# Drone.net
KiCad netlist of a schematic drawn in Altium Designer
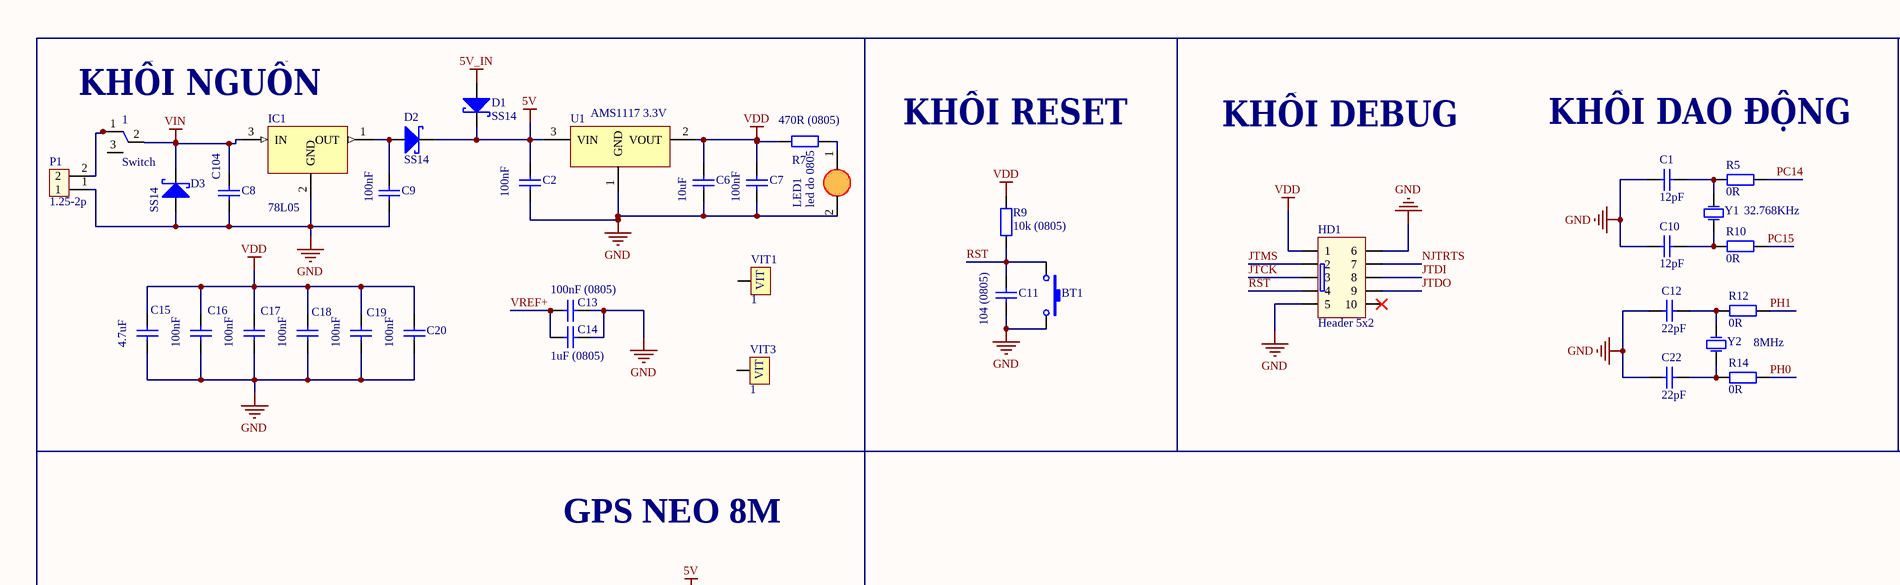
[diagram p0: Drone.SchDoc, top left]
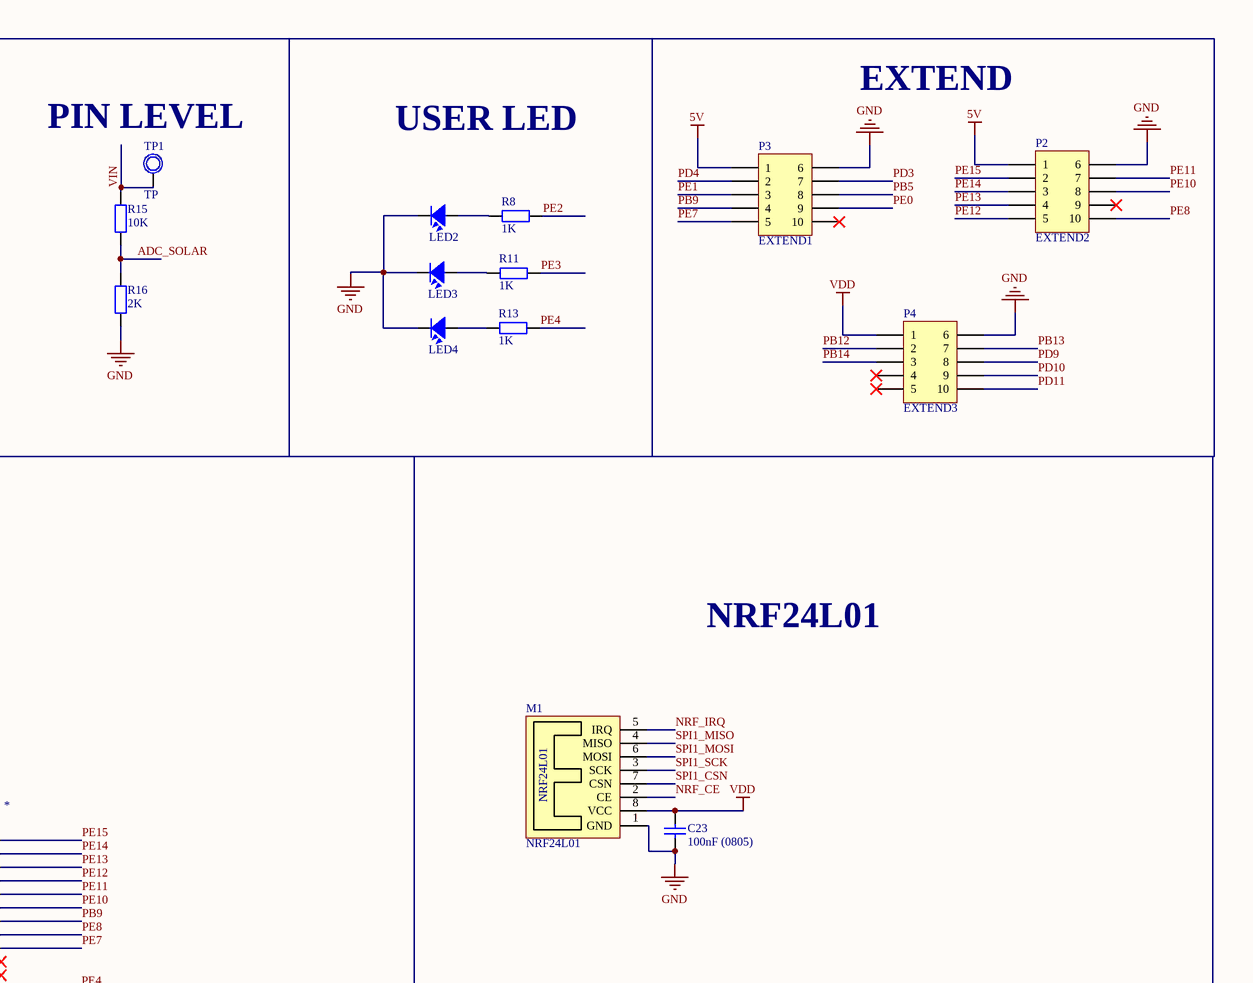
[diagram p1: Drone.SchDoc, top right]
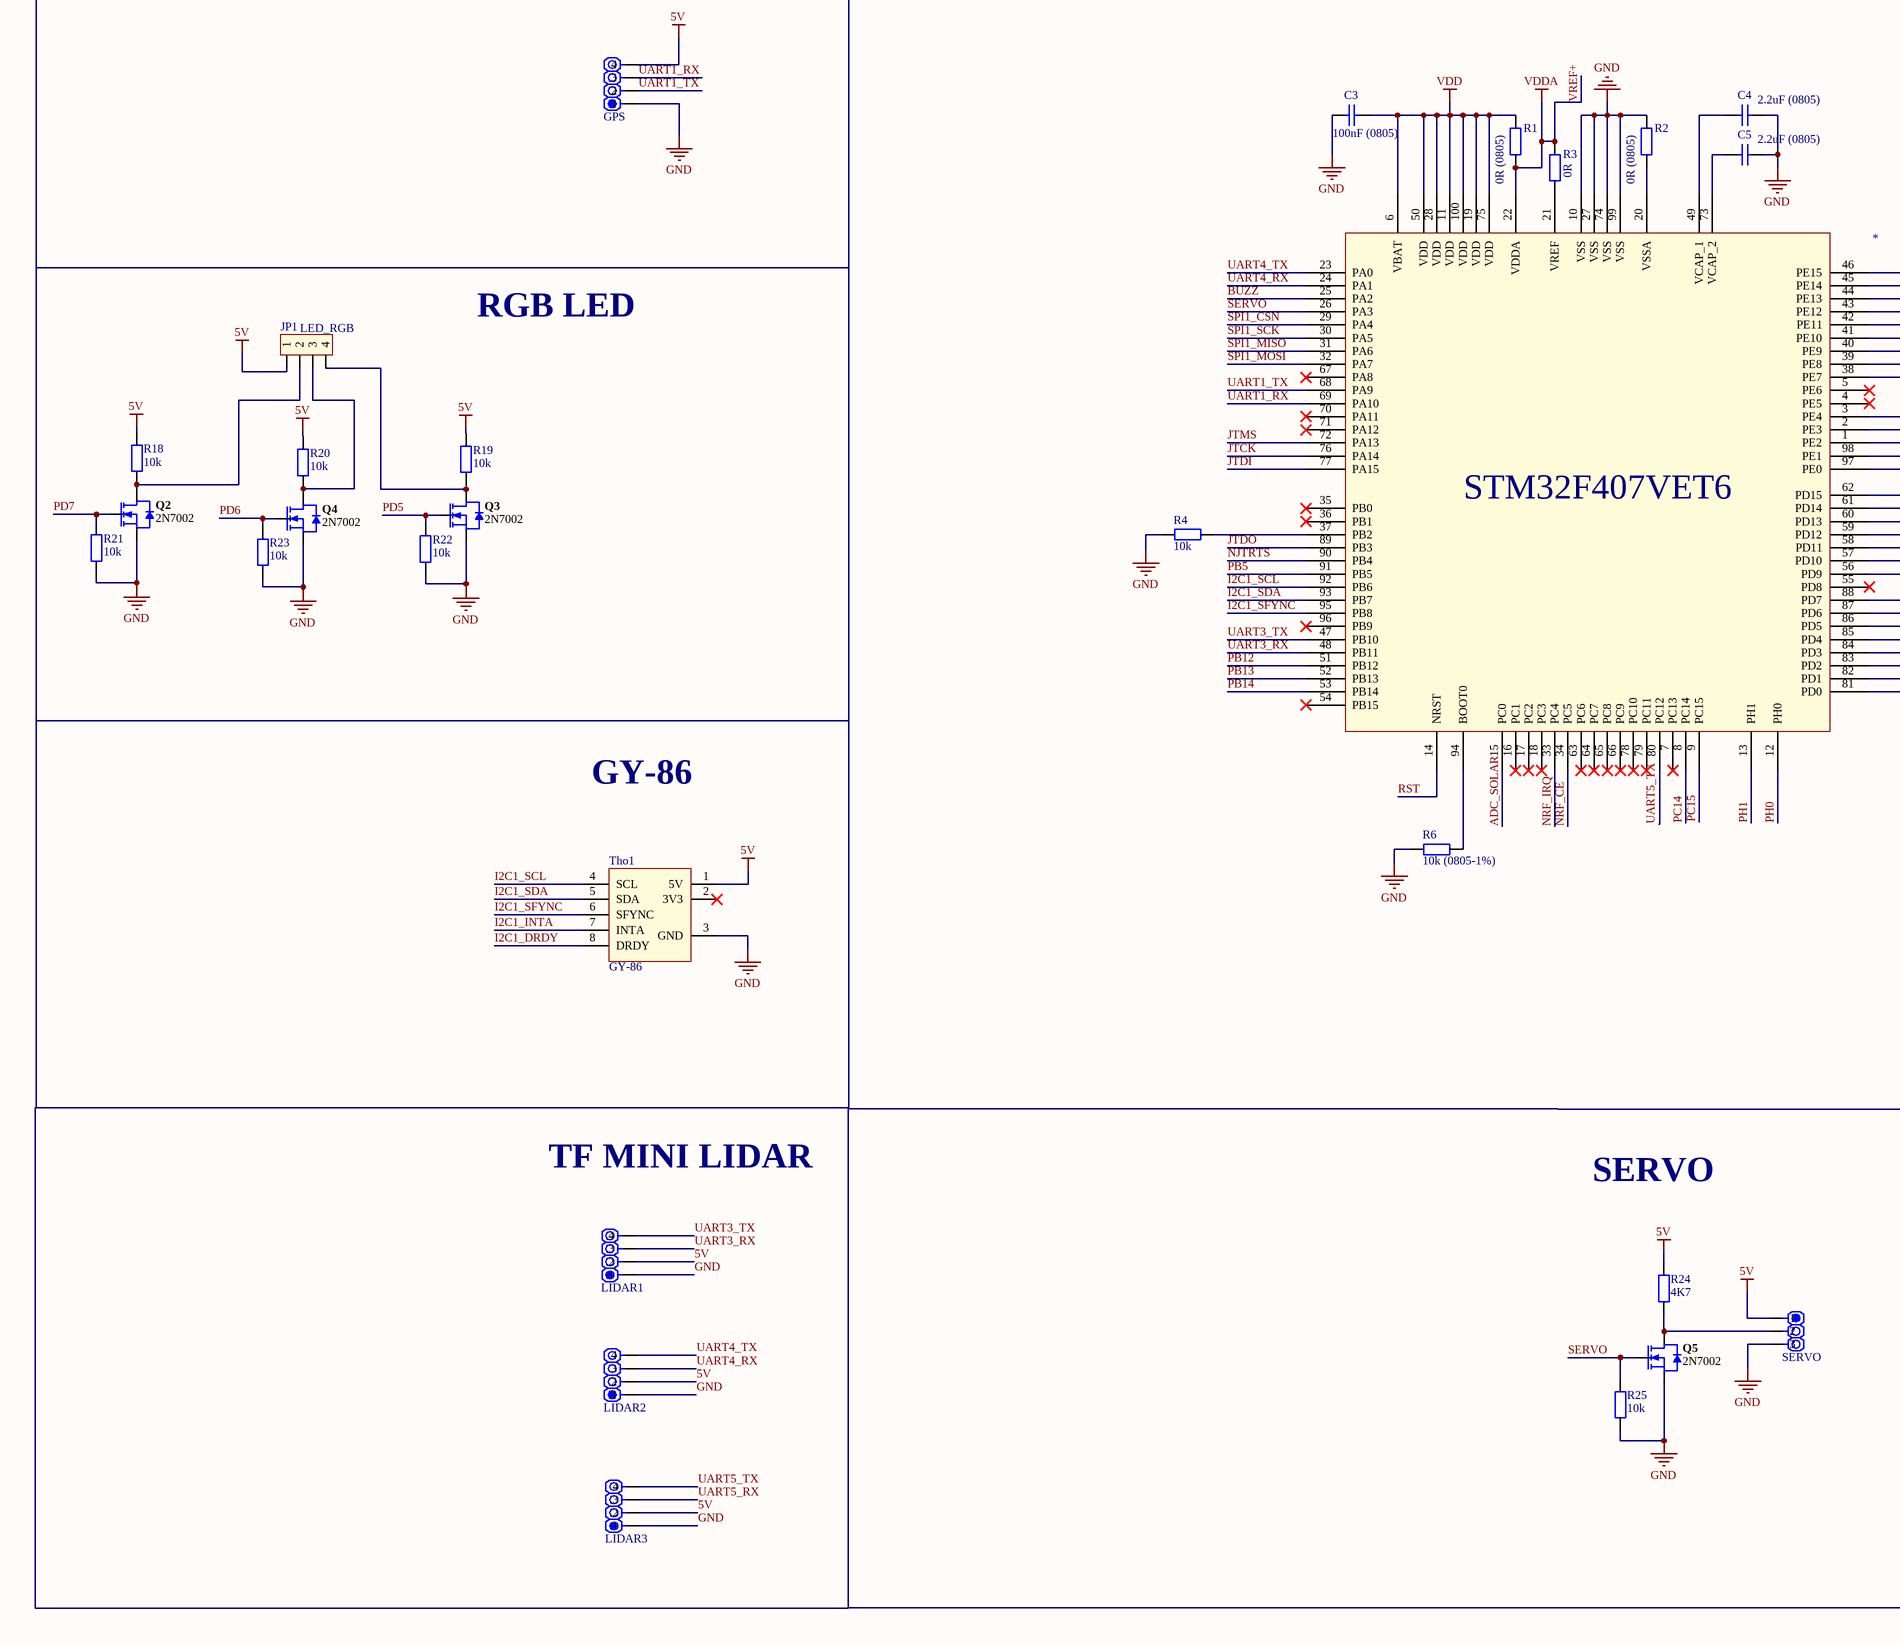
[diagram p2: Drone.SchDoc, bottom left]
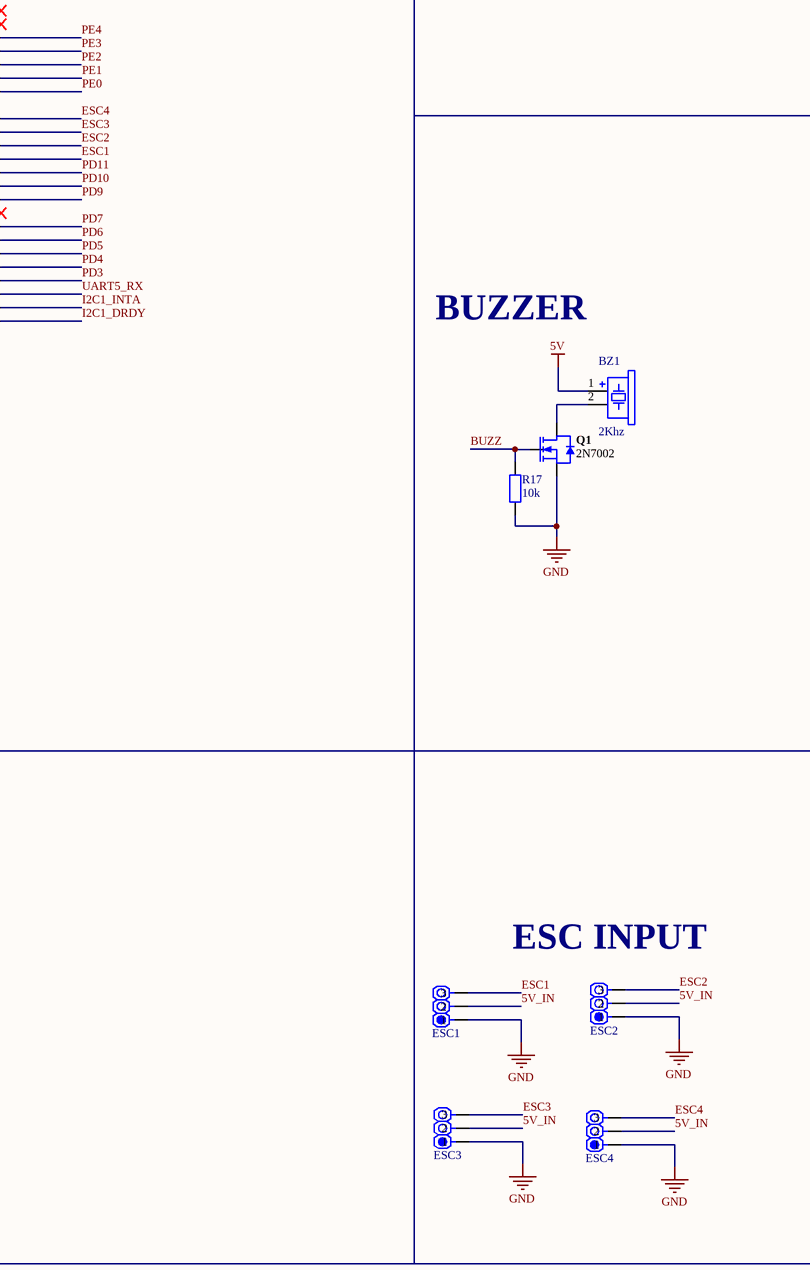
[diagram p3: Drone.SchDoc, bottom right]

(export (version "E")
  (design (tool "Eeschema 10.0.6"))
  (components
    (comp (ref "*")
      (value "STM32F407")
      (footprint "STM32F407Vet6")
      (libsource (lib "STM32f407") (part "STM32F407"))
    )
    (comp (ref "1") (value "Switch") (footprint "SW_MSS") (libsource (lib "JOYSTICK") (part "Switch")))
    (comp (ref "BT1")
      (value "Nút Nhấn 2 Chân 3x6x2.5MM SMD")
      (footprint "Nut Nhan 2 Chan SMD_N")
      (description "Dán")
      (libsource (lib "SCH Chuan") (part "Nut Nhan 2 Chan SMD"))
    )
    (comp (ref "BZ1")
      (value "2Khz")
      (footprint "coi xung")
      (description "Cắm")
      (libsource (lib "SCH Chuan") (part "Coi xung 2Khz"))
    )
    (comp (ref "C1")
      (value "12pF")
      (footprint "tu 0805")
      (description "Dán")
      (libsource (lib "SCH Chuan") (part "Tu 0805 10pF 50V 10%"))
    )
    (comp (ref "C2")
      (value "100nF")
      (footprint "tu 0805")
      (description "Dán")
      (libsource (lib "SCH Chuan") (part "Tu 0805 104 50V 10%"))
    )
    (comp (ref "C3")
      (value "100nF (0805)")
      (footprint "tu 0805")
      (description "Dán")
      (libsource (lib "SCH Chuan") (part "Tu 0805 220nF 50V 10%"))
    )
    (comp (ref "C4")
      (value "2.2uF (0805)")
      (footprint "tu 0805")
      (description "Dán")
      (libsource (lib "SCH Chuan") (part "Tu 0805 220nF 50V 10%"))
    )
    (comp (ref "C5")
      (value "2.2uF (0805)")
      (footprint "tu 0805")
      (description "Dán")
      (libsource (lib "SCH Chuan") (part "Tu 0805 220nF 50V 10%"))
    )
    (comp (ref "C6")
      (value "10uF")
      (footprint "tu 0805")
      (description "Dán")
      (libsource (lib "SCH Chuan") (part "Tu 0805 104 50V 10%"))
    )
    (comp (ref "C7")
      (value "100nF")
      (footprint "tu 0805")
      (description "Dán")
      (libsource (lib "SCH Chuan") (part "Tu 0805 104 50V 10%"))
    )
    (comp (ref "C8")
      (value "C104")
      (footprint "tu 0805")
      (description "Dán")
      (libsource (lib "SCH Chuan") (part "Tu 0805 104 50V 10%"))
    )
    (comp (ref "C9")
      (value "100nF")
      (footprint "tu 0805")
      (description "Dán")
      (libsource (lib "SCH Chuan") (part "Tu 0805 104 50V 10%"))
    )
    (comp (ref "C10")
      (value "12pF")
      (footprint "tu 0805")
      (description "Dán")
      (libsource (lib "SCH Chuan") (part "Tu 0805 10pF 50V 10%"))
    )
    (comp (ref "C11")
      (value "104 (0805)")
      (footprint "tu 0805")
      (description "Dán")
      (libsource (lib "SCH Chuan") (part "Tu 0805 104 50V 10%"))
    )
    (comp (ref "C12")
      (value "22pF")
      (footprint "tu 0805")
      (description "Dán")
      (libsource (lib "SCH Chuan") (part "Tu 0805 10pF 50V 10%"))
    )
    (comp (ref "C13")
      (value "100nF (0805)")
      (footprint "tu 0805")
      (description "Dán")
      (libsource (lib "SCH Chuan") (part "Tu 0805 220nF 50V 10%"))
    )
    (comp (ref "C14")
      (value "1uF (0805)")
      (footprint "tu 0805")
      (description "Dán")
      (libsource (lib "SCH Chuan") (part "Tu 0805 220nF 50V 10%"))
    )
    (comp (ref "C15")
      (value "4.7uF")
      (footprint "tu 0805")
      (description "Dán")
      (libsource (lib "SCH Chuan") (part "Tu 0805 104 50V 10%"))
    )
    (comp (ref "C16")
      (value "100nF")
      (footprint "tu 0805")
      (description "Dán")
      (libsource (lib "SCH Chuan") (part "Tu 0805 104 50V 10%"))
    )
    (comp (ref "C17")
      (value "100nF")
      (footprint "tu 0805")
      (description "Dán")
      (libsource (lib "SCH Chuan") (part "Tu 0805 104 50V 10%"))
    )
    (comp (ref "C18")
      (value "100nF")
      (footprint "tu 0805")
      (description "Dán")
      (libsource (lib "SCH Chuan") (part "Tu 0805 104 50V 10%"))
    )
    (comp (ref "C19")
      (value "100nF")
      (footprint "tu 0805")
      (description "Dán")
      (libsource (lib "SCH Chuan") (part "Tu 0805 104 50V 10%"))
    )
    (comp (ref "C20")
      (value "100nF")
      (footprint "tu 0805")
      (description "Dán")
      (libsource (lib "SCH Chuan") (part "Tu 0805 104 50V 10%"))
    )
    (comp (ref "C22")
      (value "22pF")
      (footprint "tu 0805")
      (description "Dán")
      (libsource (lib "SCH Chuan") (part "Tu 0805 10pF 50V 10%"))
    )
    (comp (ref "C23")
      (value "100nF (0805)")
      (footprint "tu 0805")
      (description "Dán")
      (libsource (lib "SCH Chuan") (part "Tu 0805 220nF 50V 10%"))
    )
    (comp (ref "D1")
      (value "SS14")
      (footprint "DIODE SMD")
      (description "Dán")
      (libsource (lib "SCH Chuan") (part "Diode SS14 ( 1N5819)"))
    )
    (comp (ref "D2")
      (value "SS14")
      (footprint "DIODE SMD")
      (description "Dán")
      (libsource (lib "SCH Chuan") (part "Diode SS14 ( 1N5819)"))
    )
    (comp (ref "D3")
      (value "SS14")
      (footprint "DIODE SMD")
      (description "Dán")
      (libsource (lib "SCH Chuan") (part "Diode SS14 ( 1N5819)"))
    )
    (comp (ref "ESC1")
      (value "IO")
      (footprint "CON.HDR1X3")
      (description "Header 1x3")
      (fields (field (name "PUBLISHER") "NKIM"))
      (libsource (lib "VPMyLibrary") (part "CON.HDR1x3"))
    )
    (comp (ref "ESC2")
      (value "IO")
      (footprint "CON.HDR1X3")
      (description "Header 1x3")
      (fields (field (name "PUBLISHER") "NKIM"))
      (libsource (lib "VPMyLibrary") (part "CON.HDR1x3"))
    )
    (comp (ref "ESC3")
      (value "IO")
      (footprint "CON.HDR1X3")
      (description "Header 1x3")
      (fields (field (name "PUBLISHER") "NKIM"))
      (libsource (lib "VPMyLibrary") (part "CON.HDR1x3"))
    )
    (comp (ref "ESC4")
      (value "IO")
      (footprint "CON.HDR1X3")
      (description "Header 1x3")
      (fields (field (name "PUBLISHER") "NKIM"))
      (libsource (lib "VPMyLibrary") (part "CON.HDR1x3"))
    )
    (comp (ref "GPS")
      (value "IO")
      (footprint "CON.HDR1X4L")
      (description "Header 1x4")
      (fields (field (name "PUBLISHER") "NKIM"))
      (libsource (lib "VPMyLibrary") (part "CON.HDR1x4"))
    )
    (comp (ref "HD1")
      (value "Header 5x2")
      (footprint "Hed2X5")
      (libsource (lib "syhaunguyen") (part "HED5x2"))
    )
    (comp (ref "IC1")
      (value "78L05")
      (footprint "SOT89-150P410X160-3N")
      (description "Dán")
      (libsource (lib "SCH Chuan") (part "78L05"))
    )
    (comp (ref "JP1")
      (value "LED_RGB")
      (footprint "JUMP DON DUC 2.54_4P")
      (description "Cắm")
      (libsource (lib "NhomLib") (part "Jump Don Duc 2.54_4P"))
    )
    (comp (ref "LED1")
      (value "led do 0805")
      (footprint "led 0805")
      (description "Dán")
      (libsource (lib "SCH Chuan") (part "Led 0805 Do"))
    )
    (comp (ref "LED2")
      (value "LED SMD")
      (footprint "SM-LED-0805-Yellow")
      (libsource (lib "syhaunguyen") (part "LED-SMD-0805"))
    )
    (comp (ref "LED3")
      (value "LED SMD")
      (footprint "SM-LED-0805-Green")
      (libsource (lib "syhaunguyen") (part "LED-SMD-0805"))
    )
    (comp (ref "LED4")
      (value "LED SMD")
      (footprint "SM-LED-0805-Blue")
      (libsource (lib "syhaunguyen") (part "LED-SMD-0805"))
    )
    (comp (ref "LIDAR1")
      (value "IO")
      (footprint "CON.HDR1X4L")
      (description "Header 1x4")
      (fields (field (name "PUBLISHER") "NKIM"))
      (libsource (lib "VPMyLibrary") (part "CON.HDR1x4"))
    )
    (comp (ref "LIDAR2")
      (value "IO")
      (footprint "CON.HDR1X4L")
      (description "Header 1x4")
      (fields (field (name "PUBLISHER") "NKIM"))
      (libsource (lib "VPMyLibrary") (part "CON.HDR1x4"))
    )
    (comp (ref "LIDAR3")
      (value "IO")
      (footprint "CON.HDR1X4L")
      (description "Header 1x4")
      (fields (field (name "PUBLISHER") "NKIM"))
      (libsource (lib "VPMyLibrary") (part "CON.HDR1x4"))
    )
    (comp (ref "M1") (value "NRF24L01") (footprint "NRF24L01") (libsource (lib "LIBRARY") (part "NRF24L01")))
    (comp (ref "P1")
      (value "1.25-2p")
      (footprint "Header Duc Thang 2p 1.25")
      (description "Cắm")
      (libsource (lib "SCH Chuan") (part "Header 1.25-2p"))
    )
    (comp (ref "P2")
      (value "EXTEND2")
      (footprint "HDR2X5_CEN")
      (description "Header, 5-Pin, Dual row")
      (fields (field (name "PUBLISHER") "Altium Limited"))
      (libsource (lib "NBBLib 14-03-2012") (part "Header 5X2A"))
    )
    (comp (ref "P3")
      (value "EXTEND1")
      (footprint "HDR2X5_CEN")
      (description "Header, 5-Pin, Dual row")
      (fields (field (name "PUBLISHER") "Altium Limited"))
      (libsource (lib "NBBLib 14-03-2012") (part "Header 5X2A"))
    )
    (comp (ref "P4")
      (value "EXTEND3")
      (footprint "HDR2X5_CEN")
      (description "Header, 5-Pin, Dual row")
      (fields (field (name "PUBLISHER") "Altium Limited"))
      (libsource (lib "NBBLib 14-03-2012") (part "Header 5X2A"))
    )
    (comp (ref "Q1")
      (value "2N7002")
      (footprint "SOT23-123")
      (description "N-channel Enhancement Mode Field-effect Transistor")
      (libsource (lib "LIBRARY") (part "2N7002"))
    )
    (comp (ref "Q2")
      (value "2N7002")
      (footprint "SOT23-123")
      (description "N-channel Enhancement Mode Field-effect Transistor")
      (libsource (lib "LIBRARY") (part "2N7002"))
    )
    (comp (ref "Q3")
      (value "2N7002")
      (footprint "SOT23-123")
      (description "N-channel Enhancement Mode Field-effect Transistor")
      (libsource (lib "LIBRARY") (part "2N7002"))
    )
    (comp (ref "Q4")
      (value "2N7002")
      (footprint "SOT23-123")
      (description "N-channel Enhancement Mode Field-effect Transistor")
      (libsource (lib "LIBRARY") (part "2N7002"))
    )
    (comp (ref "Q5")
      (value "2N7002")
      (footprint "SOT23-123")
      (description "N-channel Enhancement Mode Field-effect Transistor")
      (libsource (lib "LIBRARY") (part "2N7002"))
    )
    (comp (ref "R1")
      (value "0R (0805)")
      (footprint "tro 0805")
      (description "Dán")
      (libsource (lib "SCH Chuan") (part "Tro 0805 5% 470R"))
    )
    (comp (ref "R2")
      (value "0R (0805)")
      (footprint "tro 0805")
      (description "Dán")
      (libsource (lib "SCH Chuan") (part "Tro 0805 5% 470R"))
    )
    (comp (ref "R3")
      (value "0R")
      (footprint "tro 0805")
      (description "Dán")
      (libsource (lib "SCH Chuan") (part "Tro 0805 5% 470R"))
    )
    (comp (ref "R4")
      (value "10k")
      (footprint "tro 0805")
      (description "Dán")
      (libsource (lib "SCH Chuan") (part "Tro 0805 1% 10k"))
    )
    (comp (ref "R5")
      (value "0R")
      (footprint "tro 0805")
      (description "Dán")
      (libsource (lib "SCH Chuan") (part "Tro 0805 5% 470R"))
    )
    (comp (ref "R6")
      (value "10k (0805-1%)")
      (footprint "tro 0805")
      (description "Dán")
      (libsource (lib "SCH Chuan") (part "Tro 0805 1% 10k"))
    )
    (comp (ref "R7")
      (value "470R (0805)")
      (footprint "tro 0805")
      (description "Dán")
      (libsource (lib "SCH Chuan") (part "Tro 0805 5% 470R"))
    )
    (comp (ref "R8")
      (value "1K")
      (footprint "tro 0805")
      (description "Dán")
      (libsource (lib "SCH Chuan") (part "Tro 0805 5% 470R"))
    )
    (comp (ref "R9")
      (value "10k (0805)")
      (footprint "tro 0805")
      (description "Dán")
      (libsource (lib "SCH Chuan") (part "Tro 0805 5% 10k"))
    )
    (comp (ref "R10")
      (value "0R")
      (footprint "tro 0805")
      (description "Dán")
      (libsource (lib "SCH Chuan") (part "Tro 0805 5% 470R"))
    )
    (comp (ref "R11")
      (value "1K")
      (footprint "tro 0805")
      (description "Dán")
      (libsource (lib "SCH Chuan") (part "Tro 0805 5% 470R"))
    )
    (comp (ref "R12")
      (value "0R")
      (footprint "tro 0805")
      (description "Dán")
      (libsource (lib "SCH Chuan") (part "Tro 0805 5% 470R"))
    )
    (comp (ref "R13")
      (value "1K")
      (footprint "tro 0805")
      (description "Dán")
      (libsource (lib "SCH Chuan") (part "Tro 0805 5% 470R"))
    )
    (comp (ref "R14")
      (value "0R")
      (footprint "tro 0805")
      (description "Dán")
      (libsource (lib "SCH Chuan") (part "Tro 0805 5% 470R"))
    )
    (comp (ref "R15")
      (value "10K")
      (footprint "tro 0805")
      (description "Dán")
      (libsource (lib "SCH Chuan") (part "Tro 0805 5% 10k"))
    )
    (comp (ref "R16")
      (value "2K")
      (footprint "tro 0805")
      (description "Dán")
      (libsource (lib "SCH Chuan") (part "Tro 0805 5% 10k"))
    )
    (comp (ref "R17")
      (value "10k")
      (footprint "tro 0805")
      (description "Dán")
      (libsource (lib "SCH Chuan") (part "Tro 0805 1% 10k"))
    )
    (comp (ref "R18")
      (value "10k")
      (footprint "tro 0805")
      (description "Dán")
      (libsource (lib "SCH Chuan") (part "Tro 0805 1% 10k"))
    )
    (comp (ref "R19")
      (value "10k")
      (footprint "tro 0805")
      (description "Dán")
      (libsource (lib "SCH Chuan") (part "Tro 0805 1% 10k"))
    )
    (comp (ref "R20")
      (value "10k")
      (footprint "tro 0805")
      (description "Dán")
      (libsource (lib "SCH Chuan") (part "Tro 0805 1% 10k"))
    )
    (comp (ref "R21")
      (value "10k")
      (footprint "tro 0805")
      (description "Dán")
      (libsource (lib "SCH Chuan") (part "Tro 0805 1% 10k"))
    )
    (comp (ref "R22")
      (value "10k")
      (footprint "tro 0805")
      (description "Dán")
      (libsource (lib "SCH Chuan") (part "Tro 0805 1% 10k"))
    )
    (comp (ref "R23")
      (value "10k")
      (footprint "tro 0805")
      (description "Dán")
      (libsource (lib "SCH Chuan") (part "Tro 0805 1% 10k"))
    )
    (comp (ref "R24")
      (value "4K7")
      (footprint "tro 0805")
      (description "Dán")
      (libsource (lib "SCH Chuan") (part "Tro 0805 1% 10k"))
    )
    (comp (ref "R25")
      (value "10k")
      (footprint "tro 0805")
      (description "Dán")
      (libsource (lib "SCH Chuan") (part "Tro 0805 1% 10k"))
    )
    (comp (ref "SERVO")
      (value "IO")
      (footprint "CON.HDR1X3")
      (description "Header 1x3")
      (fields (field (name "PUBLISHER") "NKIM"))
      (libsource (lib "VPMyLibrary") (part "CON.HDR1x3"))
    )
    (comp (ref "Tho1") (value "GY-86") (footprint "GY-86") (libsource (lib "JOYSTICK") (part "GY-86")))
    (comp (ref "TP1")
      (value "TP")
      (footprint "TP1")
      (description "Test Point")
      (libsource (lib "syhaunguyen") (part "TP1"))
    )
    (comp (ref "U1")
      (value "AMS1117 3.3V")
      (footprint "SOT223")
      (description "Dán")
      (libsource (lib "SCH Chuan") (part "AMS1117 3.3V"))
    )
    (comp (ref "VIT1")
      (value "1")
      (footprint "VIT")
      (description "Oc Vit")
      (libsource (lib "LIBRARY") (part "VIT"))
    )
    (comp (ref "VIT3")
      (value "1")
      (footprint "VIT")
      (description "Oc Vit")
      (libsource (lib "LIBRARY") (part "VIT"))
    )
    (comp (ref "Y1")
      (value "32.768KHz")
      (footprint "XT2-32.768KHz-2_V")
      (description "Dán")
      (libsource (lib "SCH Chuan") (part "Thach anh 8MHz 49S SMD"))
    )
    (comp (ref "Y2")
      (value "8MHz")
      (footprint "thach anh 49s smd")
      (description "Dán")
      (libsource (lib "SCH Chuan") (part "Thach anh 8MHz 49S SMD"))
    )
  )
  (nets
    (net (code "1") (name "/ADC_SOLAR") (class "Default")
      (node (ref "*") (pin "15") (pinfunction "PC0_15") (pintype "passive"))
      (node (ref "R15") (pin "1") (pinfunction "1_1") (pintype "passive"))
      (node (ref "R16") (pin "2") (pinfunction "2_2") (pintype "passive"))
    )
    (net (code "2") (name "/BUZZ") (class "Default")
      (node (ref "*") (pin "25") (pinfunction "PA2_25") (pintype "passive"))
      (node (ref "Q1") (pin "1") (pinfunction "G_1") (pintype "passive"))
      (node (ref "R17") (pin "2") (pinfunction "2_2") (pintype "passive"))
    )
    (net (code "3") (name "/ESC1") (class "Default")
      (node (ref "*") (pin "59") (pinfunction "PD12_59") (pintype "passive"))
      (node (ref "ESC1") (pin "3") (pinfunction "3_3") (pintype "passive"))
    )
    (net (code "4") (name "/ESC2") (class "Default")
      (node (ref "*") (pin "60") (pinfunction "PD13_60") (pintype "passive"))
      (node (ref "ESC2") (pin "3") (pinfunction "3_3") (pintype "passive"))
    )
    (net (code "5") (name "/ESC3") (class "Default")
      (node (ref "*") (pin "61") (pinfunction "PD14_61") (pintype "passive"))
      (node (ref "ESC3") (pin "3") (pinfunction "3_3") (pintype "passive"))
    )
    (net (code "6") (name "/ESC4") (class "Default")
      (node (ref "*") (pin "62") (pinfunction "PD15_62") (pintype "passive"))
      (node (ref "ESC4") (pin "3") (pinfunction "3_3") (pintype "passive"))
    )
    (net (code "7") (name "/I2C1_DRDY") (class "Default")
      (node (ref "*") (pin "81") (pinfunction "PD0_81") (pintype "passive"))
      (node (ref "Tho1") (pin "8") (pinfunction "DRDY_8") (pintype "passive"))
    )
    (net (code "8") (name "/I2C1_INTA") (class "Default")
      (node (ref "*") (pin "82") (pinfunction "PD1_82") (pintype "passive"))
      (node (ref "Tho1") (pin "7") (pinfunction "INTA_7") (pintype "passive"))
    )
    (net (code "9") (name "/I2C1_SCL") (class "Default")
      (node (ref "*") (pin "92") (pinfunction "PB6_92") (pintype "passive"))
      (node (ref "Tho1") (pin "4") (pinfunction "SCL_4") (pintype "passive"))
    )
    (net (code "10") (name "/I2C1_SDA") (class "Default")
      (node (ref "*") (pin "93") (pinfunction "PB7_93") (pintype "passive"))
      (node (ref "Tho1") (pin "5") (pinfunction "SDA_5") (pintype "passive"))
    )
    (net (code "11") (name "/I2C1_SFYNC") (class "Default")
      (node (ref "*") (pin "95") (pinfunction "PB8_95") (pintype "passive"))
      (node (ref "Tho1") (pin "6") (pinfunction "SFYNC_6") (pintype "passive"))
    )
    (net (code "12") (name "/JTCK") (class "Default")
      (node (ref "*") (pin "76") (pinfunction "PA14_76") (pintype "passive"))
      (node (ref "HD1") (pin "3") (pinfunction "3_3") (pintype "passive"))
    )
    (net (code "13") (name "/JTDI") (class "Default")
      (node (ref "*") (pin "77") (pinfunction "PA15_77") (pintype "passive"))
      (node (ref "HD1") (pin "8") (pinfunction "8_8") (pintype "passive"))
    )
    (net (code "14") (name "/JTDO") (class "Default")
      (node (ref "*") (pin "89") (pinfunction "PB3_89") (pintype "passive"))
      (node (ref "HD1") (pin "9") (pinfunction "9_9") (pintype "passive"))
    )
    (net (code "15") (name "/JTMS") (class "Default")
      (node (ref "*") (pin "72") (pinfunction "PA13_72") (pintype "passive"))
      (node (ref "HD1") (pin "2") (pinfunction "2_2") (pintype "passive"))
    )
    (net (code "16") (name "/NJTRTS") (class "Default")
      (node (ref "*") (pin "90") (pinfunction "PB4_90") (pintype "passive"))
      (node (ref "HD1") (pin "7") (pinfunction "7_7") (pintype "passive"))
    )
    (net (code "17") (name "/NRF_CE") (class "Default")
      (node (ref "*") (pin "34") (pinfunction "PC5_34") (pintype "passive"))
      (node (ref "M1") (pin "2") (pinfunction "CE_2") (pintype "passive"))
    )
    (net (code "18") (name "/NRF_IRQ") (class "Default")
      (node (ref "*") (pin "33") (pinfunction "PC4_33") (pintype "passive"))
      (node (ref "M1") (pin "5") (pinfunction "IRQ_5") (pintype "passive"))
    )
    (net (code "19") (name "/PB5") (class "Default")
      (node (ref "*") (pin "91") (pinfunction "PB5_91") (pintype "passive"))
      (node (ref "P3") (pin "8") (pinfunction "8_8") (pintype "passive"))
    )
    (net (code "20") (name "/PB9") (class "Default")
      (node (ref "*") (pin "40") (pinfunction "PE9_40") (pintype "passive"))
      (node (ref "P3") (pin "4") (pinfunction "4_4") (pintype "passive"))
    )
    (net (code "21") (name "/PB12") (class "Default")
      (node (ref "*") (pin "51") (pinfunction "PB12_51") (pintype "passive"))
      (node (ref "P4") (pin "2") (pinfunction "2_2") (pintype "passive"))
    )
    (net (code "22") (name "/PB13") (class "Default")
      (node (ref "*") (pin "52") (pinfunction "PB13_52") (pintype "passive"))
      (node (ref "P4") (pin "7") (pinfunction "7_7") (pintype "passive"))
    )
    (net (code "23") (name "/PB14") (class "Default")
      (node (ref "*") (pin "53") (pinfunction "PB14_53") (pintype "passive"))
      (node (ref "P4") (pin "3") (pinfunction "3_3") (pintype "passive"))
    )
    (net (code "24") (name "/PC14") (class "Default")
      (node (ref "*") (pin "8") (pinfunction "PC14_8") (pintype "passive"))
      (node (ref "R5") (pin "2") (pinfunction "2_2") (pintype "passive"))
    )
    (net (code "25") (name "/PC15") (class "Default")
      (node (ref "*") (pin "9") (pinfunction "PC15_9") (pintype "passive"))
      (node (ref "R10") (pin "2") (pinfunction "2_2") (pintype "passive"))
    )
    (net (code "26") (name "/PD3") (class "Default")
      (node (ref "*") (pin "84") (pinfunction "PD3_84") (pintype "passive"))
      (node (ref "P3") (pin "7") (pinfunction "7_7") (pintype "passive"))
    )
    (net (code "27") (name "/PD4") (class "Default")
      (node (ref "*") (pin "85") (pinfunction "PD4_85") (pintype "passive"))
      (node (ref "P3") (pin "2") (pinfunction "2_2") (pintype "passive"))
    )
    (net (code "28") (name "/PD5") (class "Default")
      (node (ref "*") (pin "86") (pinfunction "PD5_86") (pintype "passive"))
      (node (ref "Q3") (pin "1") (pinfunction "G_1") (pintype "passive"))
      (node (ref "R22") (pin "2") (pinfunction "2_2") (pintype "passive"))
    )
    (net (code "29") (name "/PD6") (class "Default")
      (node (ref "*") (pin "87") (pinfunction "PD6_87") (pintype "passive"))
      (node (ref "Q4") (pin "1") (pinfunction "G_1") (pintype "passive"))
      (node (ref "R23") (pin "2") (pinfunction "2_2") (pintype "passive"))
    )
    (net (code "30") (name "/PD7") (class "Default")
      (node (ref "*") (pin "88") (pinfunction "PD7_88") (pintype "passive"))
      (node (ref "Q2") (pin "1") (pinfunction "G_1") (pintype "passive"))
      (node (ref "R21") (pin "2") (pinfunction "2_2") (pintype "passive"))
    )
    (net (code "31") (name "/PD9") (class "Default")
      (node (ref "*") (pin "56") (pinfunction "PD9_56") (pintype "passive"))
      (node (ref "P4") (pin "8") (pinfunction "8_8") (pintype "passive"))
    )
    (net (code "32") (name "/PD10") (class "Default")
      (node (ref "*") (pin "57") (pinfunction "PD10_57") (pintype "passive"))
      (node (ref "P4") (pin "9") (pinfunction "9_9") (pintype "passive"))
    )
    (net (code "33") (name "/PD11") (class "Default")
      (node (ref "*") (pin "58") (pinfunction "PD11_58") (pintype "passive"))
      (node (ref "P4") (pin "10") (pinfunction "10_10") (pintype "passive"))
    )
    (net (code "34") (name "/PE0") (class "Default")
      (node (ref "*") (pin "97") (pinfunction "PE0_97") (pintype "passive"))
      (node (ref "P3") (pin "9") (pinfunction "9_9") (pintype "passive"))
    )
    (net (code "35") (name "/PE1") (class "Default")
      (node (ref "*") (pin "98") (pinfunction "PE1_98") (pintype "passive"))
      (node (ref "P3") (pin "3") (pinfunction "3_3") (pintype "passive"))
    )
    (net (code "36") (name "/PE2") (class "Default")
      (node (ref "*") (pin "1") (pinfunction "PE2_1") (pintype "passive"))
      (node (ref "R8") (pin "2") (pinfunction "2_2") (pintype "passive"))
    )
    (net (code "37") (name "/PE3") (class "Default")
      (node (ref "*") (pin "2") (pinfunction "PE3_2") (pintype "passive"))
      (node (ref "R11") (pin "2") (pinfunction "2_2") (pintype "passive"))
    )
    (net (code "38") (name "/PE4") (class "Default")
      (node (ref "*") (pin "3") (pinfunction "PE4_3") (pintype "passive"))
      (node (ref "R13") (pin "2") (pinfunction "2_2") (pintype "passive"))
    )
    (net (code "39") (name "/PE7") (class "Default")
      (node (ref "*") (pin "38") (pinfunction "PE7_38") (pintype "passive"))
      (node (ref "P3") (pin "5") (pinfunction "5_5") (pintype "passive"))
    )
    (net (code "40") (name "/PE8") (class "Default")
      (node (ref "*") (pin "39") (pinfunction "PE8_39") (pintype "passive"))
      (node (ref "P2") (pin "10") (pinfunction "10_10") (pintype "passive"))
    )
    (net (code "41") (name "/PE10") (class "Default")
      (node (ref "*") (pin "41") (pinfunction "PE10_41") (pintype "passive"))
      (node (ref "P2") (pin "8") (pinfunction "8_8") (pintype "passive"))
    )
    (net (code "42") (name "/PE11") (class "Default")
      (node (ref "*") (pin "42") (pinfunction "PE11_42") (pintype "passive"))
      (node (ref "P2") (pin "7") (pinfunction "7_7") (pintype "passive"))
    )
    (net (code "43") (name "/PE12") (class "Default")
      (node (ref "*") (pin "43") (pinfunction "PE12_43") (pintype "passive"))
      (node (ref "P2") (pin "5") (pinfunction "5_5") (pintype "passive"))
    )
    (net (code "44") (name "/PE13") (class "Default")
      (node (ref "*") (pin "44") (pinfunction "PE13_44") (pintype "passive"))
      (node (ref "P2") (pin "4") (pinfunction "4_4") (pintype "passive"))
    )
    (net (code "45") (name "/PE14") (class "Default")
      (node (ref "*") (pin "45") (pinfunction "PE14_45") (pintype "passive"))
      (node (ref "P2") (pin "3") (pinfunction "3_3") (pintype "passive"))
    )
    (net (code "46") (name "/PE15") (class "Default")
      (node (ref "*") (pin "46") (pinfunction "PE15_46") (pintype "passive"))
      (node (ref "P2") (pin "2") (pinfunction "2_2") (pintype "passive"))
    )
    (net (code "47") (name "/PH0") (class "Default")
      (node (ref "*") (pin "12") (pinfunction "PH0_12") (pintype "passive"))
      (node (ref "R14") (pin "2") (pinfunction "2_2") (pintype "passive"))
    )
    (net (code "48") (name "/PH1") (class "Default")
      (node (ref "*") (pin "13") (pinfunction "PH1_13") (pintype "passive"))
      (node (ref "R12") (pin "2") (pinfunction "2_2") (pintype "passive"))
    )
    (net (code "49") (name "/RST") (class "Default")
      (node (ref "*") (pin "14") (pinfunction "NRST_14") (pintype "passive"))
      (node (ref "BT1") (pin "1") (pinfunction "1_1") (pintype "passive"))
      (node (ref "C11") (pin "1") (pinfunction "1_1") (pintype "passive"))
      (node (ref "HD1") (pin "4") (pinfunction "4_4") (pintype "passive"))
      (node (ref "R9") (pin "1") (pinfunction "1_1") (pintype "passive"))
    )
    (net (code "50") (name "/SERVO") (class "Default")
      (node (ref "*") (pin "26") (pinfunction "PA3_26") (pintype "passive"))
      (node (ref "Q5") (pin "1") (pinfunction "G_1") (pintype "passive"))
      (node (ref "R25") (pin "2") (pinfunction "2_2") (pintype "passive"))
    )
    (net (code "51") (name "/SPI1_CSN") (class "Default")
      (node (ref "*") (pin "29") (pinfunction "PA4_29") (pintype "passive"))
      (node (ref "M1") (pin "7") (pinfunction "CSN_7") (pintype "passive"))
    )
    (net (code "52") (name "/SPI1_MISO") (class "Default")
      (node (ref "*") (pin "31") (pinfunction "PA6_31") (pintype "passive"))
      (node (ref "M1") (pin "4") (pinfunction "MISO_4") (pintype "passive"))
    )
    (net (code "53") (name "/SPI1_MOSI") (class "Default")
      (node (ref "*") (pin "32") (pinfunction "PA7_32") (pintype "passive"))
      (node (ref "M1") (pin "6") (pinfunction "MOSI_6") (pintype "passive"))
    )
    (net (code "54") (name "/SPI1_SCK") (class "Default")
      (node (ref "*") (pin "30") (pinfunction "PA5_30") (pintype "passive"))
      (node (ref "M1") (pin "3") (pinfunction "SCK_3") (pintype "passive"))
    )
    (net (code "55") (name "/UART1_RX") (class "Default")
      (node (ref "*") (pin "69") (pinfunction "PA10_69") (pintype "passive"))
      (node (ref "GPS") (pin "3") (pinfunction "3_3") (pintype "passive"))
    )
    (net (code "56") (name "/UART1_TX") (class "Default")
      (node (ref "*") (pin "68") (pinfunction "PA9_68") (pintype "passive"))
      (node (ref "GPS") (pin "2") (pinfunction "2_2") (pintype "passive"))
    )
    (net (code "57") (name "/UART3_RX") (class "Default")
      (node (ref "*") (pin "48") (pinfunction "PB11_48") (pintype "passive"))
      (node (ref "LIDAR1") (pin "3") (pinfunction "3_3") (pintype "passive"))
    )
    (net (code "58") (name "/UART3_TX") (class "Default")
      (node (ref "*") (pin "47") (pinfunction "PB10_47") (pintype "passive"))
      (node (ref "LIDAR1") (pin "4") (pinfunction "4_4") (pintype "passive"))
    )
    (net (code "59") (name "/UART4_RX") (class "Default")
      (node (ref "*") (pin "24") (pinfunction "PA1_24") (pintype "passive"))
      (node (ref "LIDAR2") (pin "3") (pinfunction "3_3") (pintype "passive"))
    )
    (net (code "60") (name "/UART4_TX") (class "Default")
      (node (ref "*") (pin "23") (pinfunction "PA0_23") (pintype "passive"))
      (node (ref "LIDAR2") (pin "4") (pinfunction "4_4") (pintype "passive"))
    )
    (net (code "61") (name "/UART5_RX") (class "Default")
      (node (ref "*") (pin "83") (pinfunction "PD2_83") (pintype "passive"))
      (node (ref "LIDAR3") (pin "3") (pinfunction "3_3") (pintype "passive"))
    )
    (net (code "62") (name "/UART5_TX") (class "Default")
      (node (ref "*") (pin "80") (pinfunction "PC12_80") (pintype "passive"))
      (node (ref "LIDAR3") (pin "4") (pinfunction "4_4") (pintype "passive"))
    )
    (net (code "63") (name "5V") (class "Default")
      (node (ref "BZ1") (pin "1") (pinfunction "1_1") (pintype "passive"))
      (node (ref "C2") (pin "1") (pinfunction "1_1") (pintype "passive"))
      (node (ref "D1") (pin "2") (pinfunction "K_2") (pintype "passive"))
      (node (ref "D2") (pin "2") (pinfunction "K_2") (pintype "passive"))
      (node (ref "GPS") (pin "4") (pinfunction "4_4") (pintype "passive"))
      (node (ref "JP1") (pin "1") (pinfunction "1_1") (pintype "passive"))
      (node (ref "LIDAR1") (pin "2") (pinfunction "2_2") (pintype "passive"))
      (node (ref "LIDAR2") (pin "2") (pinfunction "2_2") (pintype "passive"))
      (node (ref "LIDAR3") (pin "2") (pinfunction "2_2") (pintype "passive"))
      (node (ref "P2") (pin "1") (pinfunction "1_1") (pintype "passive"))
      (node (ref "P3") (pin "1") (pinfunction "1_1") (pintype "passive"))
      (node (ref "R18") (pin "2") (pinfunction "2_2") (pintype "passive"))
      (node (ref "R19") (pin "2") (pinfunction "2_2") (pintype "passive"))
      (node (ref "R20") (pin "2") (pinfunction "2_2") (pintype "passive"))
      (node (ref "R24") (pin "2") (pinfunction "2_2") (pintype "passive"))
      (node (ref "SERVO") (pin "1") (pinfunction "1_1") (pintype "passive"))
      (node (ref "Tho1") (pin "1") (pinfunction "5V_1") (pintype "passive"))
      (node (ref "U1") (pin "3") (pinfunction "VIN_3") (pintype "passive"))
    )
    (net (code "64") (name "5V_IN") (class "Default")
      (node (ref "D1") (pin "1") (pinfunction "A_1") (pintype "passive"))
      (node (ref "ESC1") (pin "2") (pinfunction "2_2") (pintype "passive"))
      (node (ref "ESC2") (pin "2") (pinfunction "2_2") (pintype "passive"))
      (node (ref "ESC3") (pin "2") (pinfunction "2_2") (pintype "passive"))
      (node (ref "ESC4") (pin "2") (pinfunction "2_2") (pintype "passive"))
    )
    (net (code "65") (name "GND") (class "Default")
      (node (ref "*") (pin "10") (pinfunction "VSS_10") (pintype "passive"))
      (node (ref "*") (pin "27") (pinfunction "VSS_27") (pintype "passive"))
      (node (ref "*") (pin "74") (pinfunction "VSS_74") (pintype "passive"))
      (node (ref "*") (pin "99") (pinfunction "VSS_99") (pintype "passive"))
      (node (ref "BT1") (pin "2") (pinfunction "2_2") (pintype "passive"))
      (node (ref "C1") (pin "2") (pinfunction "2_2") (pintype "passive"))
      (node (ref "C10") (pin "2") (pinfunction "2_2") (pintype "passive"))
      (node (ref "C11") (pin "2") (pinfunction "2_2") (pintype "passive"))
      (node (ref "C12") (pin "2") (pinfunction "2_2") (pintype "passive"))
      (node (ref "C13") (pin "1") (pinfunction "1_1") (pintype "passive"))
      (node (ref "C14") (pin "1") (pinfunction "1_1") (pintype "passive"))
      (node (ref "C15") (pin "2") (pinfunction "2_2") (pintype "passive"))
      (node (ref "C16") (pin "2") (pinfunction "2_2") (pintype "passive"))
      (node (ref "C17") (pin "2") (pinfunction "2_2") (pintype "passive"))
      (node (ref "C18") (pin "2") (pinfunction "2_2") (pintype "passive"))
      (node (ref "C19") (pin "2") (pinfunction "2_2") (pintype "passive"))
      (node (ref "C2") (pin "2") (pinfunction "2_2") (pintype "passive"))
      (node (ref "C20") (pin "2") (pinfunction "2_2") (pintype "passive"))
      (node (ref "C22") (pin "2") (pinfunction "2_2") (pintype "passive"))
      (node (ref "C23") (pin "2") (pinfunction "2_2") (pintype "passive"))
      (node (ref "C3") (pin "2") (pinfunction "2_2") (pintype "passive"))
      (node (ref "C4") (pin "1") (pinfunction "1_1") (pintype "passive"))
      (node (ref "C5") (pin "1") (pinfunction "1_1") (pintype "passive"))
      (node (ref "C6") (pin "2") (pinfunction "2_2") (pintype "passive"))
      (node (ref "C7") (pin "2") (pinfunction "2_2") (pintype "passive"))
      (node (ref "C8") (pin "2") (pinfunction "2_2") (pintype "passive"))
      (node (ref "C9") (pin "2") (pinfunction "2_2") (pintype "passive"))
      (node (ref "D3") (pin "1") (pinfunction "A_1") (pintype "passive"))
      (node (ref "ESC1") (pin "1") (pinfunction "1_1") (pintype "passive"))
      (node (ref "ESC2") (pin "1") (pinfunction "1_1") (pintype "passive"))
      (node (ref "ESC3") (pin "1") (pinfunction "1_1") (pintype "passive"))
      (node (ref "ESC4") (pin "1") (pinfunction "1_1") (pintype "passive"))
      (node (ref "GPS") (pin "1") (pinfunction "1_1") (pintype "passive"))
      (node (ref "HD1") (pin "5") (pinfunction "5_5") (pintype "passive"))
      (node (ref "HD1") (pin "6") (pinfunction "6_6") (pintype "passive"))
      (node (ref "IC1") (pin "2") (pinfunction "GND_2") (pintype "passive"))
      (node (ref "LED1") (pin "2") (pinfunction "K_2") (pintype "passive"))
      (node (ref "LED2") (pin "2") (pinfunction "2_2") (pintype "passive"))
      (node (ref "LED3") (pin "2") (pinfunction "2_2") (pintype "passive"))
      (node (ref "LED4") (pin "2") (pinfunction "2_2") (pintype "passive"))
      (node (ref "LIDAR1") (pin "1") (pinfunction "1_1") (pintype "passive"))
      (node (ref "LIDAR2") (pin "1") (pinfunction "1_1") (pintype "passive"))
      (node (ref "LIDAR3") (pin "1") (pinfunction "1_1") (pintype "passive"))
      (node (ref "M1") (pin "1") (pinfunction "GND_1") (pintype "passive"))
      (node (ref "P1") (pin "1") (pinfunction "1_1") (pintype "passive"))
      (node (ref "P2") (pin "6") (pinfunction "6_6") (pintype "passive"))
      (node (ref "P3") (pin "6") (pinfunction "6_6") (pintype "passive"))
      (node (ref "P4") (pin "6") (pinfunction "6_6") (pintype "passive"))
      (node (ref "Q1") (pin "3") (pinfunction "S_3") (pintype "passive"))
      (node (ref "Q2") (pin "3") (pinfunction "S_3") (pintype "passive"))
      (node (ref "Q3") (pin "3") (pinfunction "S_3") (pintype "passive"))
      (node (ref "Q4") (pin "3") (pinfunction "S_3") (pintype "passive"))
      (node (ref "Q5") (pin "3") (pinfunction "S_3") (pintype "passive"))
      (node (ref "R16") (pin "1") (pinfunction "1_1") (pintype "passive"))
      (node (ref "R17") (pin "1") (pinfunction "1_1") (pintype "passive"))
      (node (ref "R2") (pin "2") (pinfunction "2_2") (pintype "passive"))
      (node (ref "R21") (pin "1") (pinfunction "1_1") (pintype "passive"))
      (node (ref "R22") (pin "1") (pinfunction "1_1") (pintype "passive"))
      (node (ref "R23") (pin "1") (pinfunction "1_1") (pintype "passive"))
      (node (ref "R25") (pin "1") (pinfunction "1_1") (pintype "passive"))
      (node (ref "R4") (pin "1") (pinfunction "1_1") (pintype "passive"))
      (node (ref "R6") (pin "1") (pinfunction "1_1") (pintype "passive"))
      (node (ref "SERVO") (pin "3") (pinfunction "3_3") (pintype "passive"))
      (node (ref "Tho1") (pin "3") (pinfunction "GND_3") (pintype "passive"))
      (node (ref "U1") (pin "1") (pinfunction "GND_1") (pintype "passive"))
    )
    (net (code "66") (name "Net-(*-BOOT0)") (class "Default")
      (node (ref "*") (pin "94") (pinfunction "BOOT0_94") (pintype "passive"))
      (node (ref "R6") (pin "2") (pinfunction "2_2") (pintype "passive"))
    )
    (net (code "67") (name "Net-(*-PB2)") (class "Default")
      (node (ref "*") (pin "37") (pinfunction "PB2_37") (pintype "passive"))
      (node (ref "R4") (pin "2") (pinfunction "2_2") (pintype "passive"))
    )
    (net (code "68") (name "Net-(*-VCAP_1)") (class "Default")
      (node (ref "*") (pin "49") (pinfunction "VCAP_1_49") (pintype "passive"))
      (node (ref "C4") (pin "2") (pinfunction "2_2") (pintype "passive"))
    )
    (net (code "69") (name "Net-(*-VCAP_2)") (class "Default")
      (node (ref "*") (pin "73") (pinfunction "VCAP_2_73") (pintype "passive"))
      (node (ref "C5") (pin "2") (pinfunction "2_2") (pintype "passive"))
    )
    (net (code "70") (name "Net-(*-VREF)") (class "Default")
      (node (ref "*") (pin "21") (pinfunction "VREF_21") (pintype "passive"))
      (node (ref "R3") (pin "1") (pinfunction "1_1") (pintype "passive"))
    )
    (net (code "71") (name "Net-(*-VSSA)") (class "Default")
      (node (ref "*") (pin "20") (pinfunction "VSSA_20") (pintype "passive"))
      (node (ref "R2") (pin "1") (pinfunction "1_1") (pintype "passive"))
    )
    (net (code "72") (name "Net-(1-Pad1)") (class "Default")
      (node (ref "1") (pin "1") (pinfunction "1_1") (pintype "passive"))
      (node (ref "P1") (pin "2") (pinfunction "2_2") (pintype "passive"))
    )
    (net (code "73") (name "Net-(D2-A)") (class "Default")
      (node (ref "C9") (pin "1") (pinfunction "1_1") (pintype "passive"))
      (node (ref "D2") (pin "1") (pinfunction "A_1") (pintype "passive"))
      (node (ref "IC1") (pin "1") (pinfunction "OUT_1") (pintype "output"))
    )
    (net (code "74") (name "Net-(LED1-A)") (class "Default")
      (node (ref "LED1") (pin "1") (pinfunction "A_1") (pintype "passive"))
      (node (ref "R7") (pin "2") (pinfunction "2_2") (pintype "passive"))
    )
    (net (code "75") (name "Net-(LED2-Pad1)") (class "Default")
      (node (ref "LED2") (pin "1") (pinfunction "1_1") (pintype "passive"))
      (node (ref "R8") (pin "1") (pinfunction "1_1") (pintype "passive"))
    )
    (net (code "76") (name "Net-(LED3-Pad1)") (class "Default")
      (node (ref "LED3") (pin "1") (pinfunction "1_1") (pintype "passive"))
      (node (ref "R11") (pin "1") (pinfunction "1_1") (pintype "passive"))
    )
    (net (code "77") (name "Net-(LED4-Pad1)") (class "Default")
      (node (ref "LED4") (pin "1") (pinfunction "1_1") (pintype "passive"))
      (node (ref "R13") (pin "1") (pinfunction "1_1") (pintype "passive"))
    )
    (net (code "78") (name "Net-(Q1-D)") (class "Default")
      (node (ref "BZ1") (pin "2") (pinfunction "2_2") (pintype "passive"))
      (node (ref "Q1") (pin "2") (pinfunction "D_2") (pintype "passive"))
    )
    (net (code "79") (name "Net-(Q2-D)") (class "Default")
      (node (ref "JP1") (pin "2") (pinfunction "2_2") (pintype "passive"))
      (node (ref "Q2") (pin "2") (pinfunction "D_2") (pintype "passive"))
      (node (ref "R18") (pin "1") (pinfunction "1_1") (pintype "passive"))
    )
    (net (code "80") (name "Net-(Q3-D)") (class "Default")
      (node (ref "JP1") (pin "4") (pinfunction "4_4") (pintype "passive"))
      (node (ref "Q3") (pin "2") (pinfunction "D_2") (pintype "passive"))
      (node (ref "R19") (pin "1") (pinfunction "1_1") (pintype "passive"))
    )
    (net (code "81") (name "Net-(Q4-D)") (class "Default")
      (node (ref "JP1") (pin "3") (pinfunction "3_3") (pintype "passive"))
      (node (ref "Q4") (pin "2") (pinfunction "D_2") (pintype "passive"))
      (node (ref "R20") (pin "1") (pinfunction "1_1") (pintype "passive"))
    )
    (net (code "82") (name "Net-(Q5-D)") (class "Default")
      (node (ref "Q5") (pin "2") (pinfunction "D_2") (pintype "passive"))
      (node (ref "R24") (pin "1") (pinfunction "1_1") (pintype "passive"))
      (node (ref "SERVO") (pin "2") (pinfunction "2_2") (pintype "passive"))
    )
    (net (code "83") (name "Net-(Y1-OSC1)") (class "Default")
      (node (ref "C1") (pin "1") (pinfunction "1_1") (pintype "passive"))
      (node (ref "R5") (pin "1") (pinfunction "1_1") (pintype "passive"))
      (node (ref "Y1") (pin "1") (pinfunction "OSC1_1") (pintype "passive"))
    )
    (net (code "84") (name "Net-(Y1-OSC2)") (class "Default")
      (node (ref "C10") (pin "1") (pinfunction "1_1") (pintype "passive"))
      (node (ref "R10") (pin "1") (pinfunction "1_1") (pintype "passive"))
      (node (ref "Y1") (pin "2") (pinfunction "OSC2_2") (pintype "passive"))
    )
    (net (code "85") (name "Net-(Y2-OSC1)") (class "Default")
      (node (ref "C12") (pin "1") (pinfunction "1_1") (pintype "passive"))
      (node (ref "R12") (pin "1") (pinfunction "1_1") (pintype "passive"))
      (node (ref "Y2") (pin "1") (pinfunction "OSC1_1") (pintype "passive"))
    )
    (net (code "86") (name "Net-(Y2-OSC2)") (class "Default")
      (node (ref "C22") (pin "1") (pinfunction "1_1") (pintype "passive"))
      (node (ref "R14") (pin "1") (pinfunction "1_1") (pintype "passive"))
      (node (ref "Y2") (pin "2") (pinfunction "OSC2_2") (pintype "passive"))
    )
    (net (code "87") (name "VDD") (class "Default")
      (node (ref "*") (pin "100") (pinfunction "VDD_100") (pintype "passive"))
      (node (ref "*") (pin "11") (pinfunction "VDD_11") (pintype "passive"))
      (node (ref "*") (pin "19") (pinfunction "VDD_19") (pintype "passive"))
      (node (ref "*") (pin "28") (pinfunction "VDD_28") (pintype "passive"))
      (node (ref "*") (pin "50") (pinfunction "VDD_50") (pintype "passive"))
      (node (ref "*") (pin "6") (pinfunction "VBAT_6") (pintype "passive"))
      (node (ref "*") (pin "75") (pinfunction "VDD_75") (pintype "passive"))
      (node (ref "C15") (pin "1") (pinfunction "1_1") (pintype "passive"))
      (node (ref "C16") (pin "1") (pinfunction "1_1") (pintype "passive"))
      (node (ref "C17") (pin "1") (pinfunction "1_1") (pintype "passive"))
      (node (ref "C18") (pin "1") (pinfunction "1_1") (pintype "passive"))
      (node (ref "C19") (pin "1") (pinfunction "1_1") (pintype "passive"))
      (node (ref "C20") (pin "1") (pinfunction "1_1") (pintype "passive"))
      (node (ref "C23") (pin "1") (pinfunction "1_1") (pintype "passive"))
      (node (ref "C3") (pin "1") (pinfunction "1_1") (pintype "passive"))
      (node (ref "C6") (pin "1") (pinfunction "1_1") (pintype "passive"))
      (node (ref "C7") (pin "1") (pinfunction "1_1") (pintype "passive"))
      (node (ref "HD1") (pin "1") (pinfunction "1_1") (pintype "passive"))
      (node (ref "M1") (pin "8") (pinfunction "VCC_8") (pintype "passive"))
      (node (ref "P4") (pin "1") (pinfunction "1_1") (pintype "passive"))
      (node (ref "R1") (pin "2") (pinfunction "2_2") (pintype "passive"))
      (node (ref "R7") (pin "1") (pinfunction "1_1") (pintype "passive"))
      (node (ref "R9") (pin "2") (pinfunction "2_2") (pintype "passive"))
      (node (ref "U1") (pin "2") (pinfunction "VOUT_2") (pintype "passive"))
    )
    (net (code "88") (name "VDDA") (class "Default")
      (node (ref "*") (pin "22") (pinfunction "VDDA_22") (pintype "passive"))
      (node (ref "C13") (pin "2") (pinfunction "2_2") (pintype "passive"))
      (node (ref "C14") (pin "2") (pinfunction "2_2") (pintype "passive"))
      (node (ref "R1") (pin "1") (pinfunction "1_1") (pintype "passive"))
      (node (ref "R3") (pin "2") (pinfunction "2_2") (pintype "passive"))
    )
    (net (code "89") (name "VIN") (class "Default")
      (node (ref "1") (pin "2") (pinfunction "1_2") (pintype "passive"))
      (node (ref "C8") (pin "1") (pinfunction "1_1") (pintype "passive"))
      (node (ref "D3") (pin "2") (pinfunction "K_2") (pintype "passive"))
      (node (ref "IC1") (pin "3") (pinfunction "IN_3") (pintype "input"))
      (node (ref "R15") (pin "2") (pinfunction "2_2") (pintype "passive"))
      (node (ref "TP1") (pin "1") (pinfunction "1_1") (pintype "passive"))
    )
    (net (code "90") (name "unconnected-(*-PA8-Pad67)") (class "Default")
      (node (ref "*") (pin "67") (pinfunction "PA8_67") (pintype "passive+no_connect"))
    )
    (net (code "91") (name "unconnected-(*-PA11-Pad70)") (class "Default")
      (node (ref "*") (pin "70") (pinfunction "PA11_70") (pintype "passive+no_connect"))
    )
    (net (code "92") (name "unconnected-(*-PA12-Pad71)") (class "Default")
      (node (ref "*") (pin "71") (pinfunction "PA12_71") (pintype "passive+no_connect"))
    )
    (net (code "93") (name "unconnected-(*-PB0-Pad35)") (class "Default")
      (node (ref "*") (pin "35") (pinfunction "PB0_35") (pintype "passive+no_connect"))
    )
    (net (code "94") (name "unconnected-(*-PB1-Pad36)") (class "Default")
      (node (ref "*") (pin "36") (pinfunction "PB1_36") (pintype "passive+no_connect"))
    )
    (net (code "95") (name "unconnected-(*-PB9-Pad96)") (class "Default")
      (node (ref "*") (pin "96") (pinfunction "PB9_96") (pintype "passive+no_connect"))
    )
    (net (code "96") (name "unconnected-(*-PB15-Pad54)") (class "Default")
      (node (ref "*") (pin "54") (pinfunction "PB15_54") (pintype "passive+no_connect"))
    )
    (net (code "97") (name "unconnected-(*-PC1-Pad16)") (class "Default")
      (node (ref "*") (pin "16") (pinfunction "PC1_16") (pintype "passive+no_connect"))
    )
    (net (code "98") (name "unconnected-(*-PC2-Pad17)") (class "Default")
      (node (ref "*") (pin "17") (pinfunction "PC2_17") (pintype "passive+no_connect"))
    )
    (net (code "99") (name "unconnected-(*-PC3-Pad18)") (class "Default")
      (node (ref "*") (pin "18") (pinfunction "PC3_18") (pintype "passive+no_connect"))
    )
    (net (code "100") (name "unconnected-(*-PC6-Pad63)") (class "Default")
      (node (ref "*") (pin "63") (pinfunction "PC6_63") (pintype "passive+no_connect"))
    )
    (net (code "101") (name "unconnected-(*-PC7-Pad64)") (class "Default")
      (node (ref "*") (pin "64") (pinfunction "PC7_64") (pintype "passive+no_connect"))
    )
    (net (code "102") (name "unconnected-(*-PC8-Pad65)") (class "Default")
      (node (ref "*") (pin "65") (pinfunction "PC8_65") (pintype "passive+no_connect"))
    )
    (net (code "103") (name "unconnected-(*-PC9-Pad66)") (class "Default")
      (node (ref "*") (pin "66") (pinfunction "PC9_66") (pintype "passive+no_connect"))
    )
    (net (code "104") (name "unconnected-(*-PC10-Pad78)") (class "Default")
      (node (ref "*") (pin "78") (pinfunction "PC10_78") (pintype "passive+no_connect"))
    )
    (net (code "105") (name "unconnected-(*-PC11-Pad79)") (class "Default")
      (node (ref "*") (pin "79") (pinfunction "PC11_79") (pintype "passive+no_connect"))
    )
    (net (code "106") (name "unconnected-(*-PC13-Pad7)") (class "Default")
      (node (ref "*") (pin "7") (pinfunction "PC13_7") (pintype "passive+no_connect"))
    )
    (net (code "107") (name "unconnected-(*-PD8-Pad55)") (class "Default")
      (node (ref "*") (pin "55") (pinfunction "PD8_55") (pintype "passive+no_connect"))
    )
    (net (code "108") (name "unconnected-(*-PE5-Pad4)") (class "Default")
      (node (ref "*") (pin "4") (pinfunction "PE5_4") (pintype "passive+no_connect"))
    )
    (net (code "109") (name "unconnected-(*-PE6-Pad5)") (class "Default")
      (node (ref "*") (pin "5") (pinfunction "PE6_5") (pintype "passive+no_connect"))
    )
    (net (code "110") (name "unconnected-(1-1-Pad3)") (class "Default")
      (node (ref "1") (pin "3") (pinfunction "1_3") (pintype "passive"))
    )
    (net (code "111") (name "unconnected-(HD1-Pad10)") (class "Default")
      (node (ref "HD1") (pin "10") (pinfunction "10_10") (pintype "passive+no_connect"))
    )
    (net (code "112") (name "unconnected-(P2-Pad9)") (class "Default")
      (node (ref "P2") (pin "9") (pinfunction "9_9") (pintype "passive+no_connect"))
    )
    (net (code "113") (name "unconnected-(P3-Pad10)") (class "Default")
      (node (ref "P3") (pin "10") (pinfunction "10_10") (pintype "passive+no_connect"))
    )
    (net (code "114") (name "unconnected-(P4-Pad4)") (class "Default")
      (node (ref "P4") (pin "4") (pinfunction "4_4") (pintype "passive+no_connect"))
    )
    (net (code "115") (name "unconnected-(P4-Pad5)") (class "Default")
      (node (ref "P4") (pin "5") (pinfunction "5_5") (pintype "passive+no_connect"))
    )
    (net (code "116") (name "unconnected-(Tho1-3V3-Pad2)") (class "Default")
      (node (ref "Tho1") (pin "2") (pinfunction "3V3_2") (pintype "passive+no_connect"))
    )
    (net (code "117") (name "unconnected-(VIT1-1-PadVIT1)") (class "Default")
      (node (ref "VIT1") (pin "VIT1") (pinfunction "1_VIT1") (pintype "passive"))
    )
    (net (code "118") (name "unconnected-(VIT3-1-PadVIT1)") (class "Default")
      (node (ref "VIT3") (pin "VIT1") (pinfunction "1_VIT1") (pintype "passive"))
    )
  )
)
